# SPI_Flash.net
KiCad netlist of a schematic drawn in Altium Designer
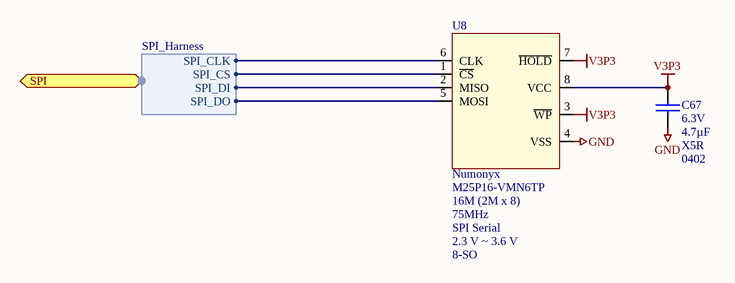
[diagram p0: SPI Flash.SchDoc]

(export (version "E")
  (design (tool "Eeschema 10.0.6"))
  (components
    (comp (ref "C67")
      (value "4.7uF")
      (footprint "C_ERA-0402")
      (description "CAP CER 4.7UF 6.3V X5R 0402")
      (fields
        (field (name "MANUFACTURER") "Murata Electronics North America")
        (field (name "MANUFACTURER PART NUMBER") "GRM155R60J475ME87D")
        (field (name "VOLTAGE - RATED") "6.3V")
        (field (name "CAPACITANCE") "4.7µF")
        (field (name "TEMPERATURE COEFFICIENT") "X5R")
        (field (name "PACKAGE / CASE") "0402")
      )
      (libsource (lib "Main LibraryX") (part "C_0402_4.7UF"))
    )
    (comp (ref "U8")
      (value "U_16MBIT_SPI_FLASH")
      (footprint "SOIC127P600X135-8L")
      (description "IC FLASH 16MBIT 75MHZ 8SOIC")
      (fields
        (field (name "MANUFACTURER") "Numonyx")
        (field (name "MANUFACTURER PART NUMBER") "M25P16-VMN6TP")
        (field (name "MEMORY SIZE") "16M (2M x 8)")
        (field (name "SPEED") "75MHz")
        (field (name "INTERFACE") "SPI Serial")
        (field (name "VOLTAGE - SUPPLY") "2.3 V ~ 3.6 V")
        (field (name "SUPPLIER DEVICE PACKAGE") "8-SO")
      )
      (libsource (lib "Main Library") (part "U_16MBIT_SPI_FLASH"))
    )
  )
  (nets
    (net (code "2") (name "/SPI_CLK") (class "Default")
      (node (ref "U8") (pin "6") (pinfunction "CLK_6") (pintype "passive"))
    )
    (net (code "3") (name "/SPI_CS") (class "Default")
      (node (ref "U8") (pin "1") (pinfunction "~{CS}_1") (pintype "passive"))
    )
    (net (code "4") (name "/SPI_DI") (class "Default")
      (node (ref "U8") (pin "2") (pinfunction "MISO_2") (pintype "passive"))
    )
    (net (code "5") (name "/SPI_DO") (class "Default")
      (node (ref "U8") (pin "5") (pinfunction "MOSI_5") (pintype "passive"))
    )
    (net (code "7") (name "GND") (class "Default")
      (node (ref "C67") (pin "1") (pinfunction "1_1") (pintype "passive"))
      (node (ref "U8") (pin "4") (pinfunction "VSS_4") (pintype "passive"))
    )
    (net (code "8") (name "V3P3") (class "Default")
      (node (ref "C67") (pin "2") (pinfunction "2_2") (pintype "passive"))
      (node (ref "U8") (pin "3") (pinfunction "~{WP}_3") (pintype "passive"))
      (node (ref "U8") (pin "7") (pinfunction "~{HOLD}_7") (pintype "passive"))
      (node (ref "U8") (pin "8") (pinfunction "VCC_8") (pintype "passive"))
    )
  )
)
